# joystick.net
KiCad netlist of a schematic drawn in EAGLE
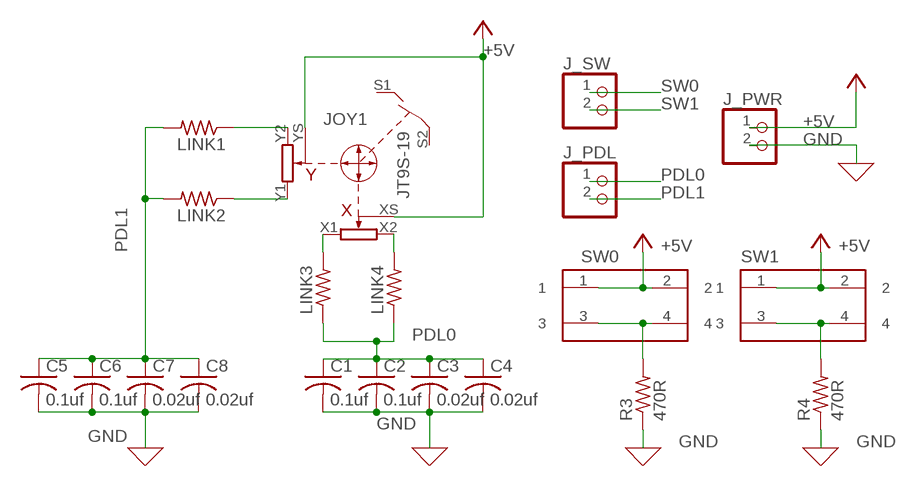
[diagram p0: schematic, sheet 1]

(export (version "E")
  (design (tool "Eeschema 10.0.6"))
  (components
    (comp (ref "C1")
      (value "0.1uf")
      (footprint "eagle-import:C0805")
      (libsource (lib "eagle-import") (part "C-USC0805"))
    )
    (comp (ref "C2")
      (value "0.1uf")
      (footprint "eagle-import:C0805")
      (libsource (lib "eagle-import") (part "C-USC0805"))
    )
    (comp (ref "C3")
      (value "0.02uf")
      (footprint "eagle-import:C0805")
      (libsource (lib "eagle-import") (part "C-USC0805"))
    )
    (comp (ref "C4")
      (value "0.02uf")
      (footprint "eagle-import:C0805")
      (libsource (lib "eagle-import") (part "C-USC0805"))
    )
    (comp (ref "C5")
      (value "0.1uf")
      (footprint "eagle-import:C0805")
      (libsource (lib "eagle-import") (part "C-USC0805"))
    )
    (comp (ref "C6")
      (value "0.1uf")
      (footprint "eagle-import:C0805")
      (libsource (lib "eagle-import") (part "C-USC0805"))
    )
    (comp (ref "C7")
      (value "0.02uf")
      (footprint "eagle-import:C0805")
      (libsource (lib "eagle-import") (part "C-USC0805"))
    )
    (comp (ref "C8")
      (value "0.02uf")
      (footprint "eagle-import:C0805")
      (libsource (lib "eagle-import") (part "C-USC0805"))
    )
    (comp (ref "JOY1")
      (value "JT9S-19")
      (footprint "eagle-import:JT9S-1P")
      (libsource (lib "eagle-import") (part "JT9S-19"))
    )
    (comp (ref "J_PDL")
      (value "PINHD-1X2")
      (footprint "eagle-import:1X02")
      (libsource (lib "eagle-import") (part "PINHD-1X2"))
    )
    (comp (ref "J_PWR")
      (value "PINHD-1X2")
      (footprint "eagle-import:1X02")
      (libsource (lib "eagle-import") (part "PINHD-1X2"))
    )
    (comp (ref "J_SW")
      (value "PINHD-1X2")
      (footprint "eagle-import:1X02")
      (libsource (lib "eagle-import") (part "PINHD-1X2"))
    )
    (comp (ref "LINK1")
      (value "0")
      (footprint "eagle-import:R0805")
      (libsource (lib "eagle-import") (part "R-US_R0805"))
    )
    (comp (ref "LINK2")
      (value "0")
      (footprint "eagle-import:R0805")
      (libsource (lib "eagle-import") (part "R-US_R0805"))
    )
    (comp (ref "LINK3")
      (value "0")
      (footprint "eagle-import:R0805")
      (libsource (lib "eagle-import") (part "R-US_R0805"))
    )
    (comp (ref "LINK4")
      (value "0")
      (footprint "eagle-import:R0805")
      (libsource (lib "eagle-import") (part "R-US_R0805"))
    )
    (comp (ref "R3")
      (value "470R")
      (footprint "eagle-import:R0805")
      (libsource (lib "eagle-import") (part "R-US_R0805"))
    )
    (comp (ref "R4")
      (value "470R")
      (footprint "eagle-import:R0805")
      (libsource (lib "eagle-import") (part "R-US_R0805"))
    )
    (comp (ref "SW0")
      (value "430476073716")
      (footprint "eagle-import:430476073716")
      (libsource (lib "eagle-import") (part "430476073716"))
    )
    (comp (ref "SW1")
      (value "430476073716")
      (footprint "eagle-import:430476073716")
      (libsource (lib "eagle-import") (part "430476073716"))
    )
  )
  (nets
    (net (code "1") (name "/PDL0") (class "Default")
      (node (ref "C1") (pin "1") (pinfunction "1_1") (pintype "passive"))
      (node (ref "C2") (pin "1") (pinfunction "1_1") (pintype "passive"))
      (node (ref "C3") (pin "1") (pinfunction "1_1") (pintype "passive"))
      (node (ref "C4") (pin "1") (pinfunction "1_1") (pintype "passive"))
      (node (ref "J_PDL") (pin "1") (pinfunction "1_1") (pintype "passive"))
      (node (ref "LINK3") (pin "1") (pinfunction "1_1") (pintype "passive"))
      (node (ref "LINK4") (pin "1") (pinfunction "1_1") (pintype "passive"))
    )
    (net (code "2") (name "/PDL1") (class "Default")
      (node (ref "C5") (pin "1") (pinfunction "1_1") (pintype "passive"))
      (node (ref "C6") (pin "1") (pinfunction "1_1") (pintype "passive"))
      (node (ref "C7") (pin "1") (pinfunction "1_1") (pintype "passive"))
      (node (ref "C8") (pin "1") (pinfunction "1_1") (pintype "passive"))
      (node (ref "J_PDL") (pin "2") (pinfunction "2_2") (pintype "passive"))
      (node (ref "LINK1") (pin "2") (pinfunction "2_2") (pintype "passive"))
      (node (ref "LINK2") (pin "2") (pinfunction "2_2") (pintype "passive"))
    )
    (net (code "3") (name "/SW0") (class "Default")
      (node (ref "J_SW") (pin "1") (pinfunction "1_1") (pintype "passive"))
      (node (ref "R3") (pin "2") (pinfunction "2_2") (pintype "passive"))
      (node (ref "SW0") (pin "3") (pinfunction "3_3") (pintype "bidirectional"))
      (node (ref "SW0") (pin "4") (pinfunction "4_4") (pintype "bidirectional"))
    )
    (net (code "4") (name "/SW1") (class "Default")
      (node (ref "J_SW") (pin "2") (pinfunction "2_2") (pintype "passive"))
      (node (ref "R4") (pin "2") (pinfunction "2_2") (pintype "passive"))
      (node (ref "SW1") (pin "3") (pinfunction "3_3") (pintype "bidirectional"))
      (node (ref "SW1") (pin "4") (pinfunction "4_4") (pintype "bidirectional"))
    )
    (net (code "5") (name "GND") (class "Default")
      (node (ref "C1") (pin "2") (pinfunction "2_2") (pintype "passive"))
      (node (ref "C2") (pin "2") (pinfunction "2_2") (pintype "passive"))
      (node (ref "C3") (pin "2") (pinfunction "2_2") (pintype "passive"))
      (node (ref "C4") (pin "2") (pinfunction "2_2") (pintype "passive"))
      (node (ref "C5") (pin "2") (pinfunction "2_2") (pintype "passive"))
      (node (ref "C6") (pin "2") (pinfunction "2_2") (pintype "passive"))
      (node (ref "C7") (pin "2") (pinfunction "2_2") (pintype "passive"))
      (node (ref "C8") (pin "2") (pinfunction "2_2") (pintype "passive"))
      (node (ref "J_PWR") (pin "2") (pinfunction "2_2") (pintype "passive"))
      (node (ref "R3") (pin "1") (pinfunction "1_1") (pintype "passive"))
      (node (ref "R4") (pin "1") (pinfunction "1_1") (pintype "passive"))
    )
    (net (code "6") (name "Net-(JOY1-PadX1)") (class "Default")
      (node (ref "JOY1") (pin "X1") (pinfunction "X1_X1") (pintype "passive"))
      (node (ref "LINK3") (pin "2") (pinfunction "2_2") (pintype "passive"))
    )
    (net (code "7") (name "Net-(JOY1-PadX2)") (class "Default")
      (node (ref "JOY1") (pin "X2") (pinfunction "X2_X2") (pintype "passive"))
      (node (ref "LINK4") (pin "2") (pinfunction "2_2") (pintype "passive"))
    )
    (net (code "8") (name "Net-(JOY1-PadY1)") (class "Default")
      (node (ref "JOY1") (pin "Y1") (pinfunction "Y1_Y1") (pintype "passive"))
      (node (ref "LINK2") (pin "1") (pinfunction "1_1") (pintype "passive"))
    )
    (net (code "9") (name "Net-(JOY1-PadY2)") (class "Default")
      (node (ref "JOY1") (pin "Y2") (pinfunction "Y2_Y2") (pintype "passive"))
      (node (ref "LINK1") (pin "1") (pinfunction "1_1") (pintype "passive"))
    )
    (net (code "10") (name "VCC") (class "Default")
      (node (ref "JOY1") (pin "XS") (pinfunction "XS_XS") (pintype "passive"))
      (node (ref "JOY1") (pin "YS") (pinfunction "YS_YS") (pintype "passive"))
      (node (ref "J_PWR") (pin "1") (pinfunction "1_1") (pintype "passive"))
      (node (ref "SW0") (pin "1") (pinfunction "1_1") (pintype "bidirectional"))
      (node (ref "SW0") (pin "2") (pinfunction "2_2") (pintype "bidirectional"))
      (node (ref "SW1") (pin "1") (pinfunction "1_1") (pintype "bidirectional"))
      (node (ref "SW1") (pin "2") (pinfunction "2_2") (pintype "bidirectional"))
    )
    (net (code "11") (name "unconnected-(JOY1-PadS1)") (class "Default")
      (node (ref "JOY1") (pin "S1") (pinfunction "S1_S1") (pintype "passive"))
    )
    (net (code "12") (name "unconnected-(JOY1-PadS2)") (class "Default")
      (node (ref "JOY1") (pin "S2") (pinfunction "S2_S2") (pintype "passive"))
    )
  )
)
